# 10_MSM8916_POWER1.net
KiCad netlist of a schematic drawn in Altium Designer
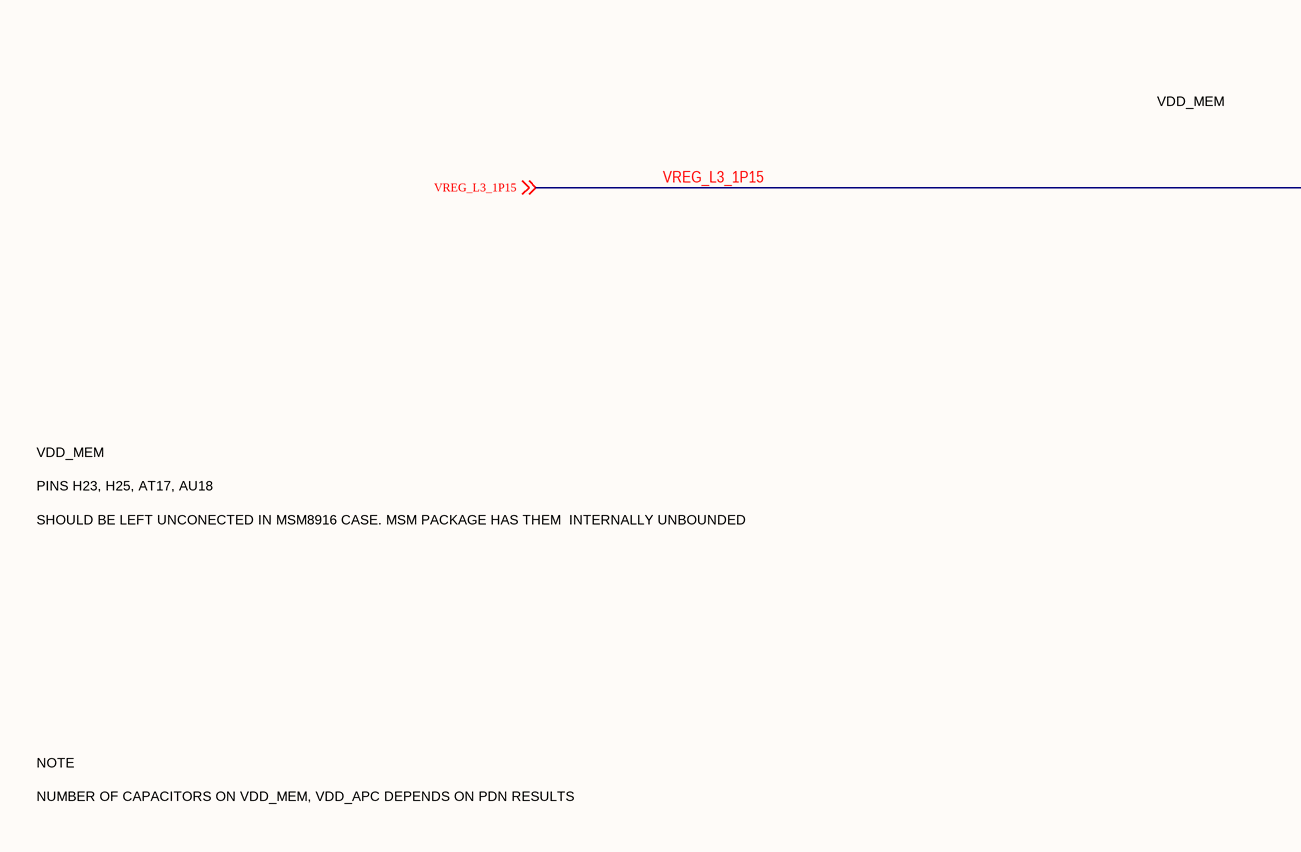
[diagram p0: 10 MSM8916_POWER1.SchDoc, top left]
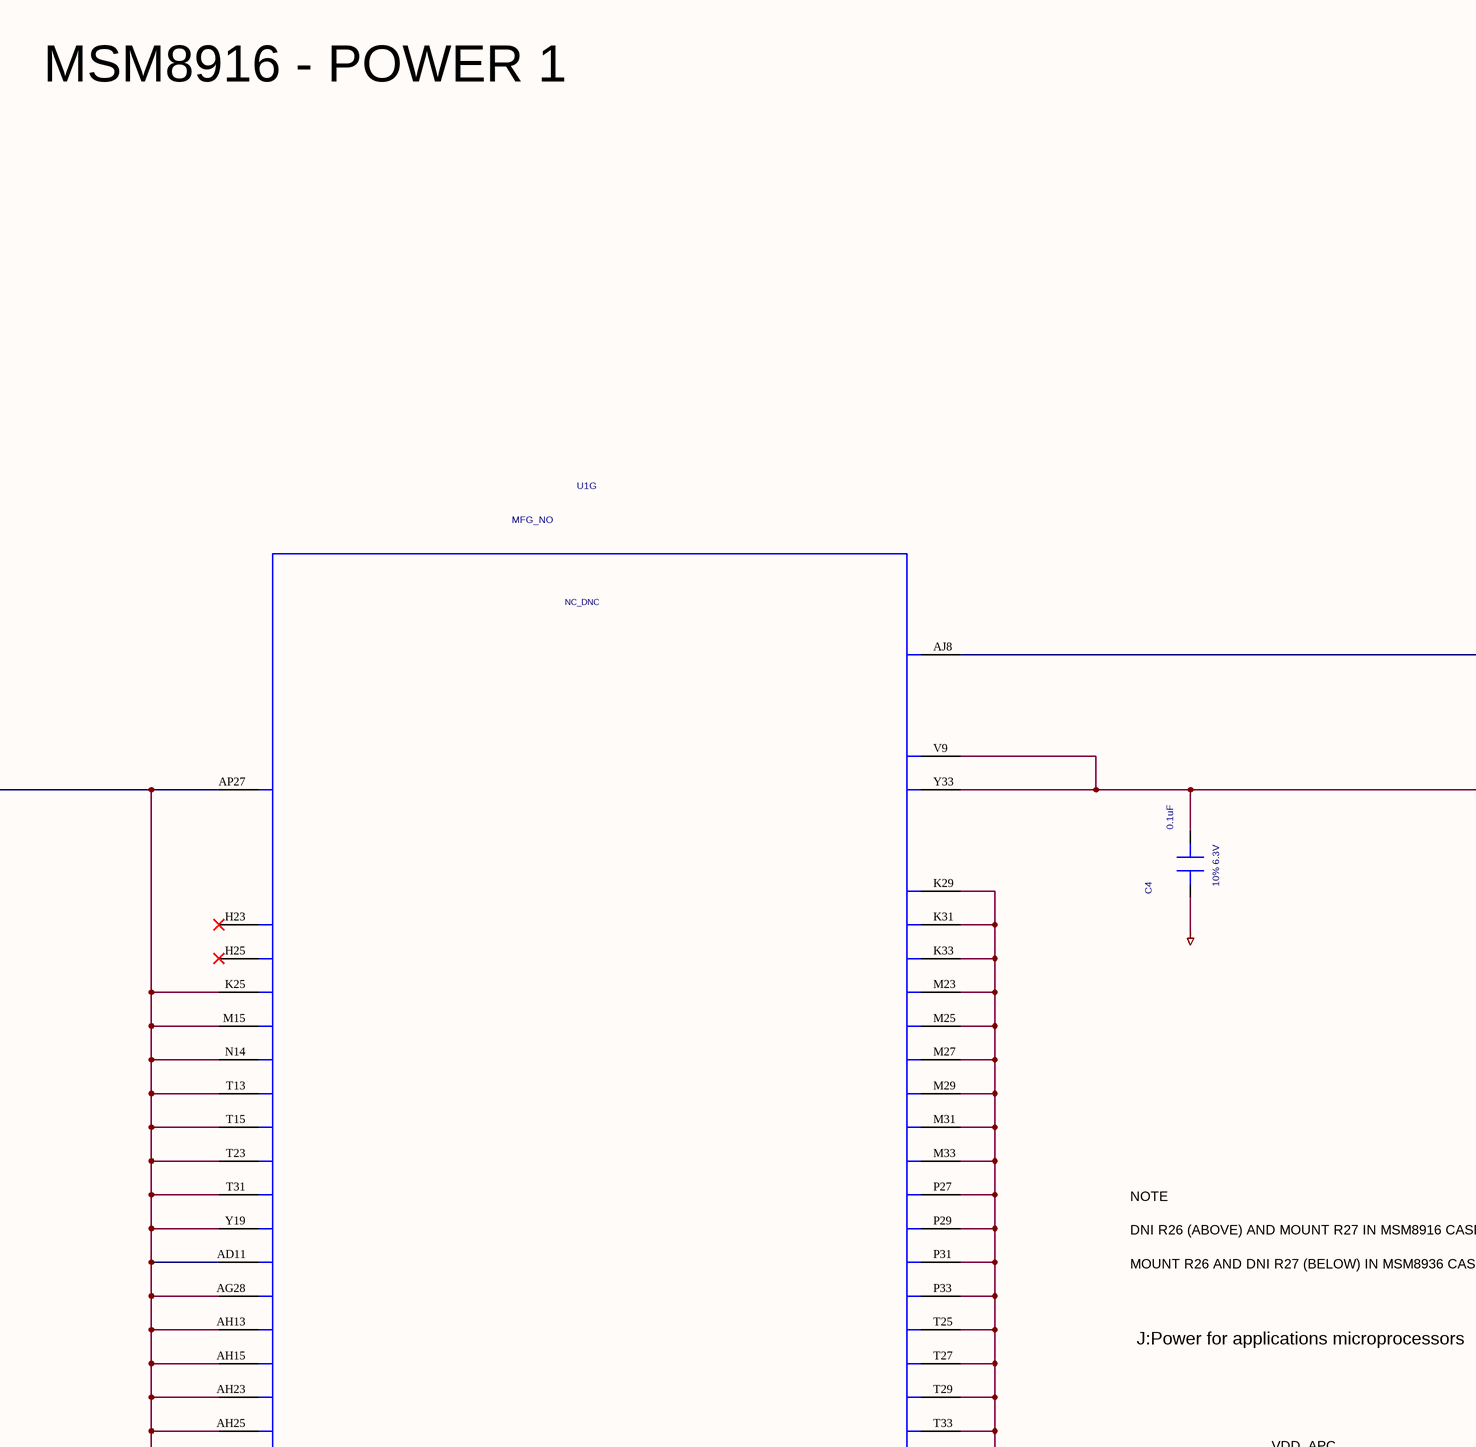
[diagram p1: 10 MSM8916_POWER1.SchDoc, top middle]
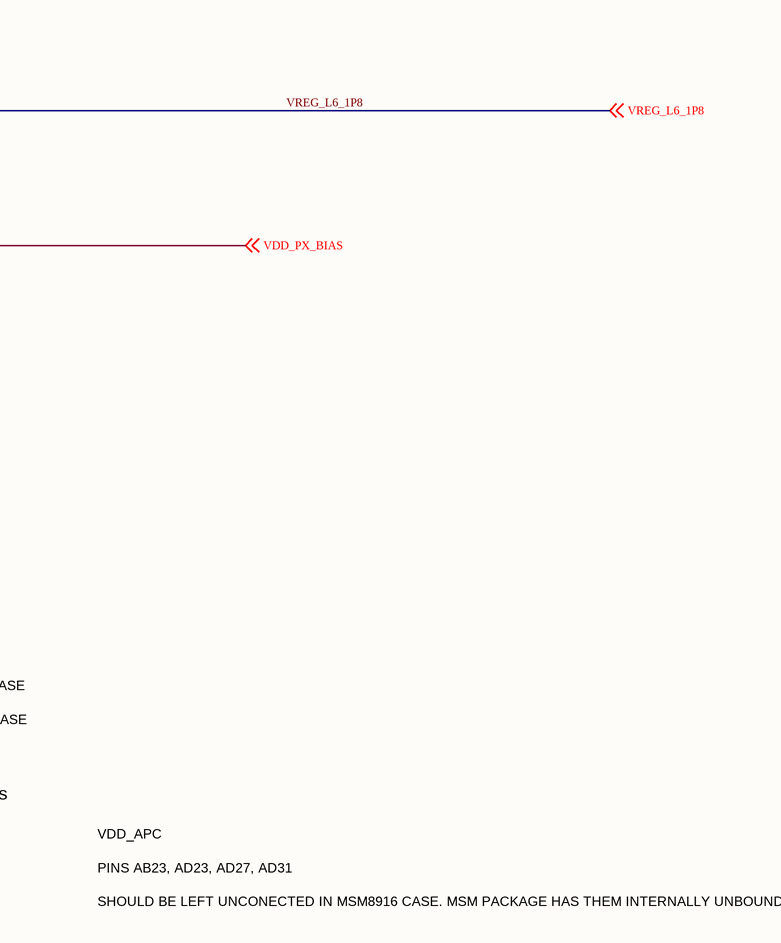
[diagram p2: 10 MSM8916_POWER1.SchDoc, top right]
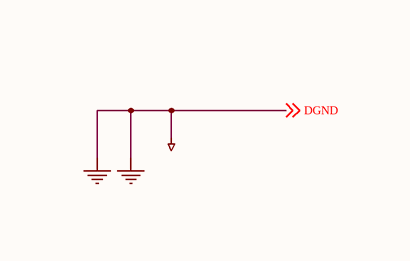
[diagram p3: 10 MSM8916_POWER1.SchDoc, bottom left]
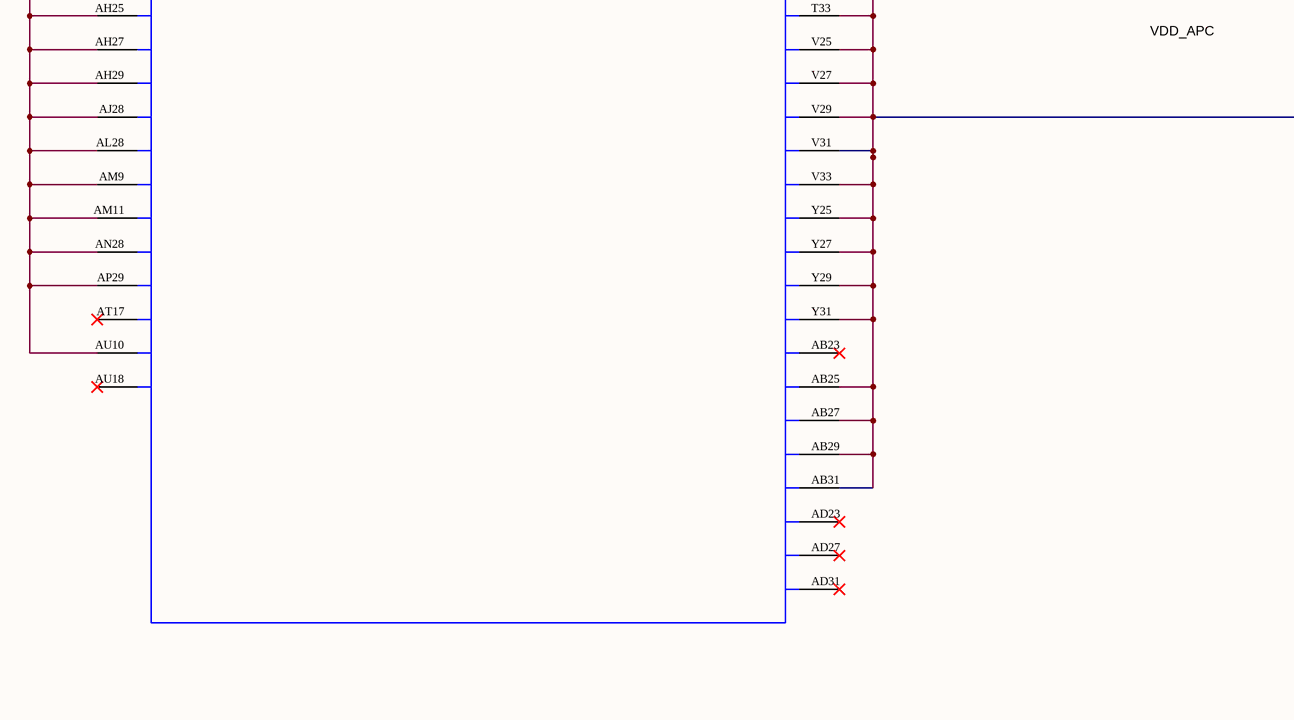
[diagram p4: 10 MSM8916_POWER1.SchDoc, bottom middle]
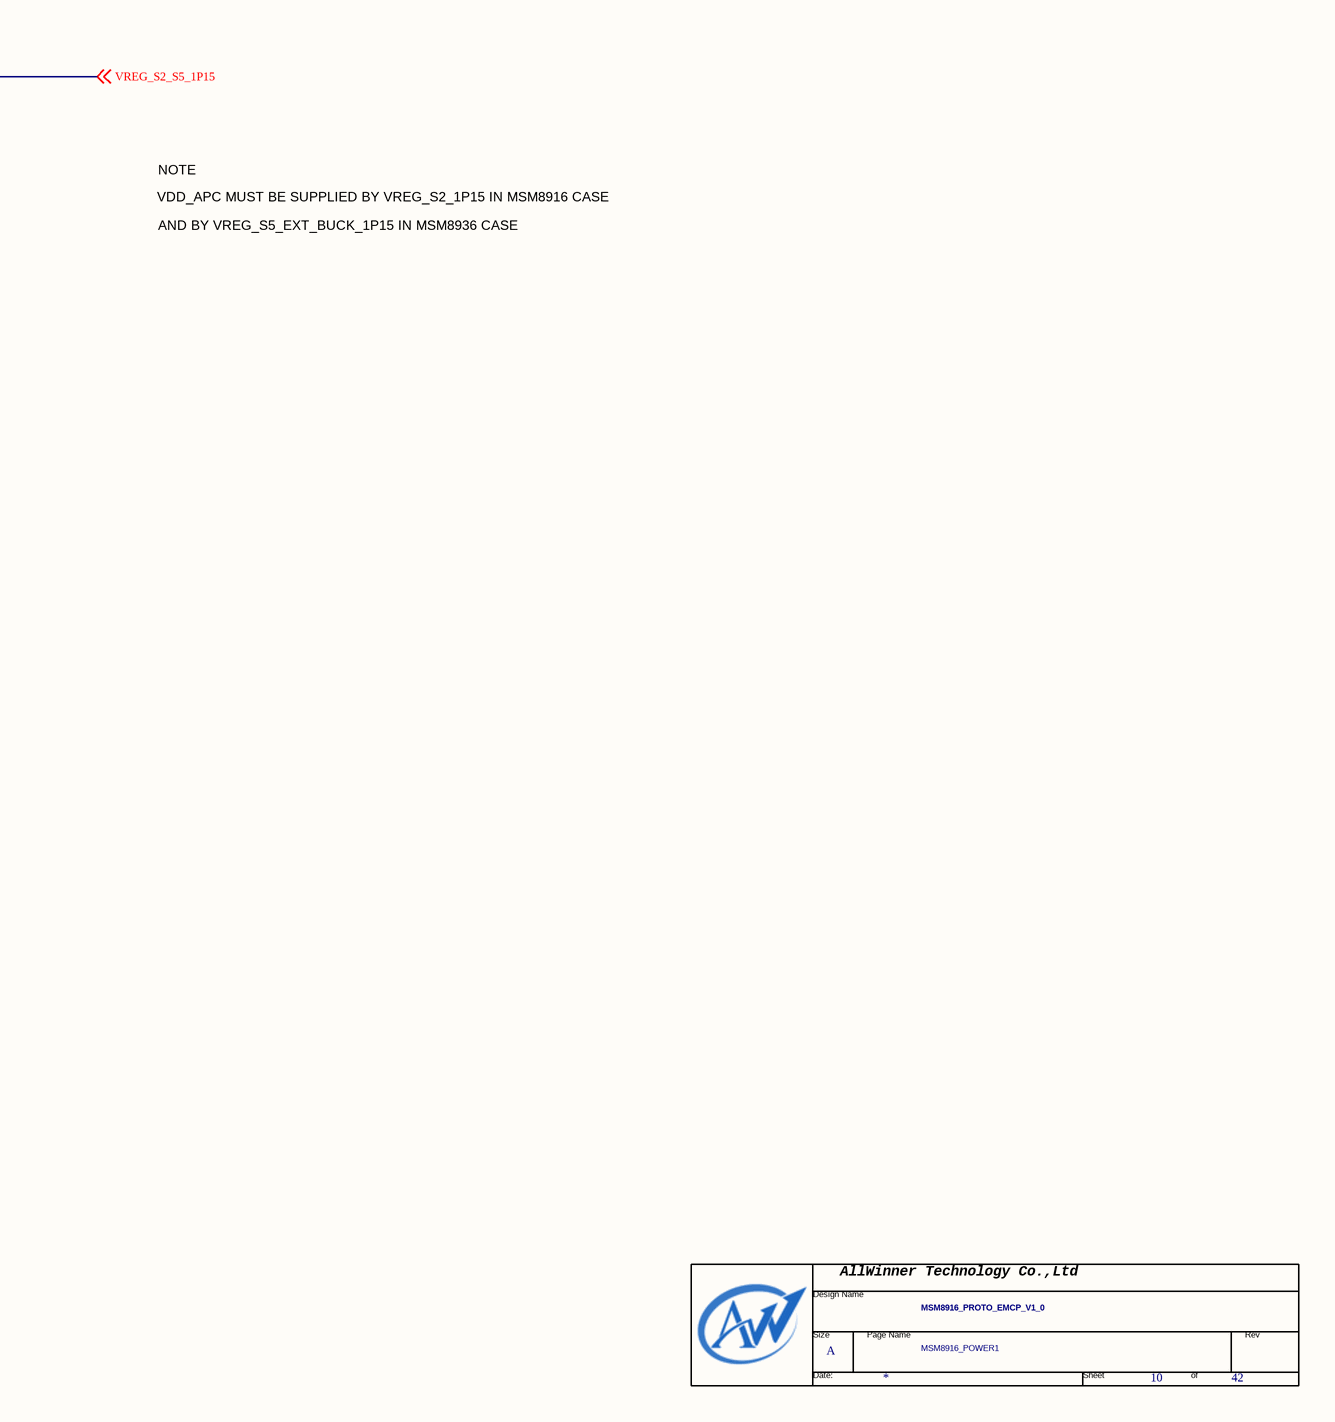
[diagram p5: 10 MSM8916_POWER1.SchDoc, bottom right]

(export (version "E")
  (design (tool "Eeschema 10.0.6"))
  (components
    (comp (ref "*")
      (value "TitleBlock0-AW")
      (fields
        (field (name "PAGE COUNT") "42")
        (field (name "PAGE NUMBER") "10")
        (field (name "PAGE SIZE") "A")
        (field (name "TITLE") "MSM8916_PROTO_EMCP_V1_0")
        (field (name "DOC") "MSM8916_POWER1")
      )
      (libsource (lib "*") (part "TitleBlock0-AW"))
    )
    (comp (ref "C4")
      (value "0.1uF")
      (fields (field (name "TOLERANCE") "10% 6.3V") (field (name "PART_NUMBER") "MCN_NO"))
      (libsource (lib "MSM8916_DRAM_PMIC_REF_Library") (part "CAP#1"))
    )
    (comp (ref "U1")
      (value "ASIC_MSM8936_760PIN")
      (footprint "MSM-8916-0-760NSP-TR-00-0")
      (fields
        (field (name "SYMNAME") "NC_DNC")
        (field (name "PART_NUMBER") "MCN_NO")
        (field (name "PART_ID") "MFG_NO")
      )
      (libsource (lib "MSM8916_DRAM_PMIC_REF_Library") (part "ASIC_MSM8936_760PIN"))
    )
  )
  (nets
    (net (code "1") (name "DGND") (class "Default")
      (node (ref "C4") (pin "1") (pinfunction "POS_1") (pintype "bidirectional"))
    )
    (net (code "2") (name "VDD_PX_BIAS") (class "Default")
      (node (ref "C4") (pin "2") (pinfunction "NEG_2") (pintype "bidirectional"))
      (node (ref "U1") (pin "V9") (pinfunction "VDDPX_VBIAS_SDC_V9") (pintype "power_in"))
      (node (ref "U1") (pin "Y33") (pinfunction "VDDPX_VBIAS_UIM_Y33") (pintype "power_in"))
    )
    (net (code "3") (name "VREG_L3_1P15") (class "Default")
      (node (ref "U1") (pin "AD11") (pinfunction "VDDMX_1_11_AD11") (pintype "power_in"))
      (node (ref "U1") (pin "AG28") (pinfunction "VDDMX_1_12_AG28") (pintype "power_in"))
      (node (ref "U1") (pin "AH13") (pinfunction "VDDMX_1_13_AH13") (pintype "power_in"))
      (node (ref "U1") (pin "AH15") (pinfunction "VDDMX_1_14_AH15") (pintype "power_in"))
      (node (ref "U1") (pin "AH23") (pinfunction "VDDMX_1_15_AH23") (pintype "power_in"))
      (node (ref "U1") (pin "AH25") (pinfunction "VDDMX_1_16_AH25") (pintype "power_in"))
      (node (ref "U1") (pin "AH27") (pinfunction "VDDMX_1_17_AH27") (pintype "power_in"))
      (node (ref "U1") (pin "AH29") (pinfunction "VDDMX_1_18_AH29") (pintype "power_in"))
      (node (ref "U1") (pin "AJ28") (pinfunction "VDDMX_1_19_AJ28") (pintype "power_in"))
      (node (ref "U1") (pin "AL28") (pinfunction "VDDMX_1_20_AL28") (pintype "power_in"))
      (node (ref "U1") (pin "AM11") (pinfunction "VDDMX_1_22_AM11") (pintype "power_in"))
      (node (ref "U1") (pin "AM9") (pinfunction "VDDMX_1_21_AM9") (pintype "power_in"))
      (node (ref "U1") (pin "AN28") (pinfunction "VDDMX_1_23_AN28") (pintype "power_in"))
      (node (ref "U1") (pin "AP27") (pinfunction "VDDMX_TXDAC_AP27") (pintype "power_in"))
      (node (ref "U1") (pin "AP29") (pinfunction "VDDMX_1_24_AP29") (pintype "power_in"))
      (node (ref "U1") (pin "AU10") (pinfunction "VDDMX_1_26_AU10") (pintype "power_in"))
      (node (ref "U1") (pin "K25") (pinfunction "VDDMX_1_3_K25") (pintype "power_in"))
      (node (ref "U1") (pin "M15") (pinfunction "VDDMX_1_4_M15") (pintype "power_in"))
      (node (ref "U1") (pin "N14") (pinfunction "VDDMX_1_5_N14") (pintype "power_in"))
      (node (ref "U1") (pin "T13") (pinfunction "VDDMX_1_6_T13") (pintype "power_in"))
      (node (ref "U1") (pin "T15") (pinfunction "VDDMX_1_7_T15") (pintype "power_in"))
      (node (ref "U1") (pin "T23") (pinfunction "VDDMX_1_8_T23") (pintype "power_in"))
      (node (ref "U1") (pin "T31") (pinfunction "VDDMX_1_9_T31") (pintype "power_in"))
      (node (ref "U1") (pin "Y19") (pinfunction "VDDMX_1_10_Y19") (pintype "power_in"))
    )
    (net (code "4") (name "VREG_L6_1P8") (class "Default")
      (node (ref "U1") (pin "AJ8") (pinfunction "QFPROM_BLOW_VDD_AJ8") (pintype "power_in"))
    )
    (net (code "5") (name "VREG_S2_S5_1P15") (class "Default")
      (node (ref "U1") (pin "AB25") (pinfunction "VDD_APC_28_AB25") (pintype "power_in"))
      (node (ref "U1") (pin "AB27") (pinfunction "VDD_APC_29_AB27") (pintype "power_in"))
      (node (ref "U1") (pin "AB29") (pinfunction "VDD_APC_30_AB29") (pintype "power_in"))
      (node (ref "U1") (pin "AB31") (pinfunction "VDD_APC_31_AB31") (pintype "power_in"))
      (node (ref "U1") (pin "K29") (pinfunction "VDD_APC_1_K29") (pintype "power_in"))
      (node (ref "U1") (pin "K31") (pinfunction "VDD_APC_2_K31") (pintype "power_in"))
      (node (ref "U1") (pin "K33") (pinfunction "VDD_APC_3_K33") (pintype "power_in"))
      (node (ref "U1") (pin "M23") (pinfunction "VDD_APC_4_M23") (pintype "power_in"))
      (node (ref "U1") (pin "M25") (pinfunction "VDD_APC_5_M25") (pintype "power_in"))
      (node (ref "U1") (pin "M27") (pinfunction "VDD_APC_6_M27") (pintype "power_in"))
      (node (ref "U1") (pin "M29") (pinfunction "VDD_APC_7_M29") (pintype "power_in"))
      (node (ref "U1") (pin "M31") (pinfunction "VDD_APC_8_M31") (pintype "power_in"))
      (node (ref "U1") (pin "M33") (pinfunction "VDD_APC_9_M33") (pintype "power_in"))
      (node (ref "U1") (pin "P27") (pinfunction "VDD_APC_10_P27") (pintype "power_in"))
      (node (ref "U1") (pin "P29") (pinfunction "VDD_APC_11_P29") (pintype "power_in"))
      (node (ref "U1") (pin "P31") (pinfunction "VDD_APC_12_P31") (pintype "power_in"))
      (node (ref "U1") (pin "P33") (pinfunction "VDD_APC_13_P33") (pintype "power_in"))
      (node (ref "U1") (pin "T25") (pinfunction "VDD_APC_14_T25") (pintype "power_in"))
      (node (ref "U1") (pin "T27") (pinfunction "VDD_APC_15_T27") (pintype "power_in"))
      (node (ref "U1") (pin "T29") (pinfunction "VDD_APC_16_T29") (pintype "power_in"))
      (node (ref "U1") (pin "T33") (pinfunction "VDD_APC_17_T33") (pintype "power_in"))
      (node (ref "U1") (pin "V25") (pinfunction "VDD_APC_18_V25") (pintype "power_in"))
      (node (ref "U1") (pin "V27") (pinfunction "VDD_APC_19_V27") (pintype "power_in"))
      (node (ref "U1") (pin "V29") (pinfunction "VDD_APC_20_V29") (pintype "power_in"))
      (node (ref "U1") (pin "V31") (pinfunction "VDD_APC_21_V31") (pintype "power_in"))
      (node (ref "U1") (pin "V33") (pinfunction "VDD_APC_22_V33") (pintype "power_in"))
      (node (ref "U1") (pin "Y25") (pinfunction "VDD_APC_23_Y25") (pintype "power_in"))
      (node (ref "U1") (pin "Y27") (pinfunction "VDD_APC_24_Y27") (pintype "power_in"))
      (node (ref "U1") (pin "Y29") (pinfunction "VDD_APC_25_Y29") (pintype "power_in"))
      (node (ref "U1") (pin "Y31") (pinfunction "VDD_APC_26_Y31") (pintype "power_in"))
    )
    (net (code "6") (name "unconnected-(U1G-VDDMX_1_1-PadH23)") (class "Default")
      (node (ref "U1") (pin "H23") (pinfunction "VDDMX_1_1_H23") (pintype "power_in+no_connect"))
    )
    (net (code "7") (name "unconnected-(U1G-VDDMX_1_2-PadH25)") (class "Default")
      (node (ref "U1") (pin "H25") (pinfunction "VDDMX_1_2_H25") (pintype "power_in+no_connect"))
    )
    (net (code "8") (name "unconnected-(U1G-VDDMX_1_25-PadAT17)") (class "Default")
      (node (ref "U1") (pin "AT17") (pinfunction "VDDMX_1_25_AT17") (pintype "power_in+no_connect"))
    )
    (net (code "9") (name "unconnected-(U1G-VDDMX_1_27-PadAU18)") (class "Default")
      (node (ref "U1") (pin "AU18") (pinfunction "VDDMX_1_27_AU18") (pintype "power_in+no_connect"))
    )
    (net (code "10") (name "unconnected-(U1G-VDD_APC_27-PadAB23)") (class "Default")
      (node (ref "U1") (pin "AB23") (pinfunction "VDD_APC_27_AB23") (pintype "power_in+no_connect"))
    )
    (net (code "11") (name "unconnected-(U1G-VDD_APC_32-PadAD23)") (class "Default")
      (node (ref "U1") (pin "AD23") (pinfunction "VDD_APC_32_AD23") (pintype "power_in+no_connect"))
    )
    (net (code "12") (name "unconnected-(U1G-VDD_APC_33-PadAD27)") (class "Default")
      (node (ref "U1") (pin "AD27") (pinfunction "VDD_APC_33_AD27") (pintype "power_in+no_connect"))
    )
    (net (code "13") (name "unconnected-(U1G-VDD_APC_34-PadAD31)") (class "Default")
      (node (ref "U1") (pin "AD31") (pinfunction "VDD_APC_34_AD31") (pintype "power_in+no_connect"))
    )
  )
)
